# USB_Hub_PCB.net
KiCad netlist of a schematic drawn in EasyEDA Pro
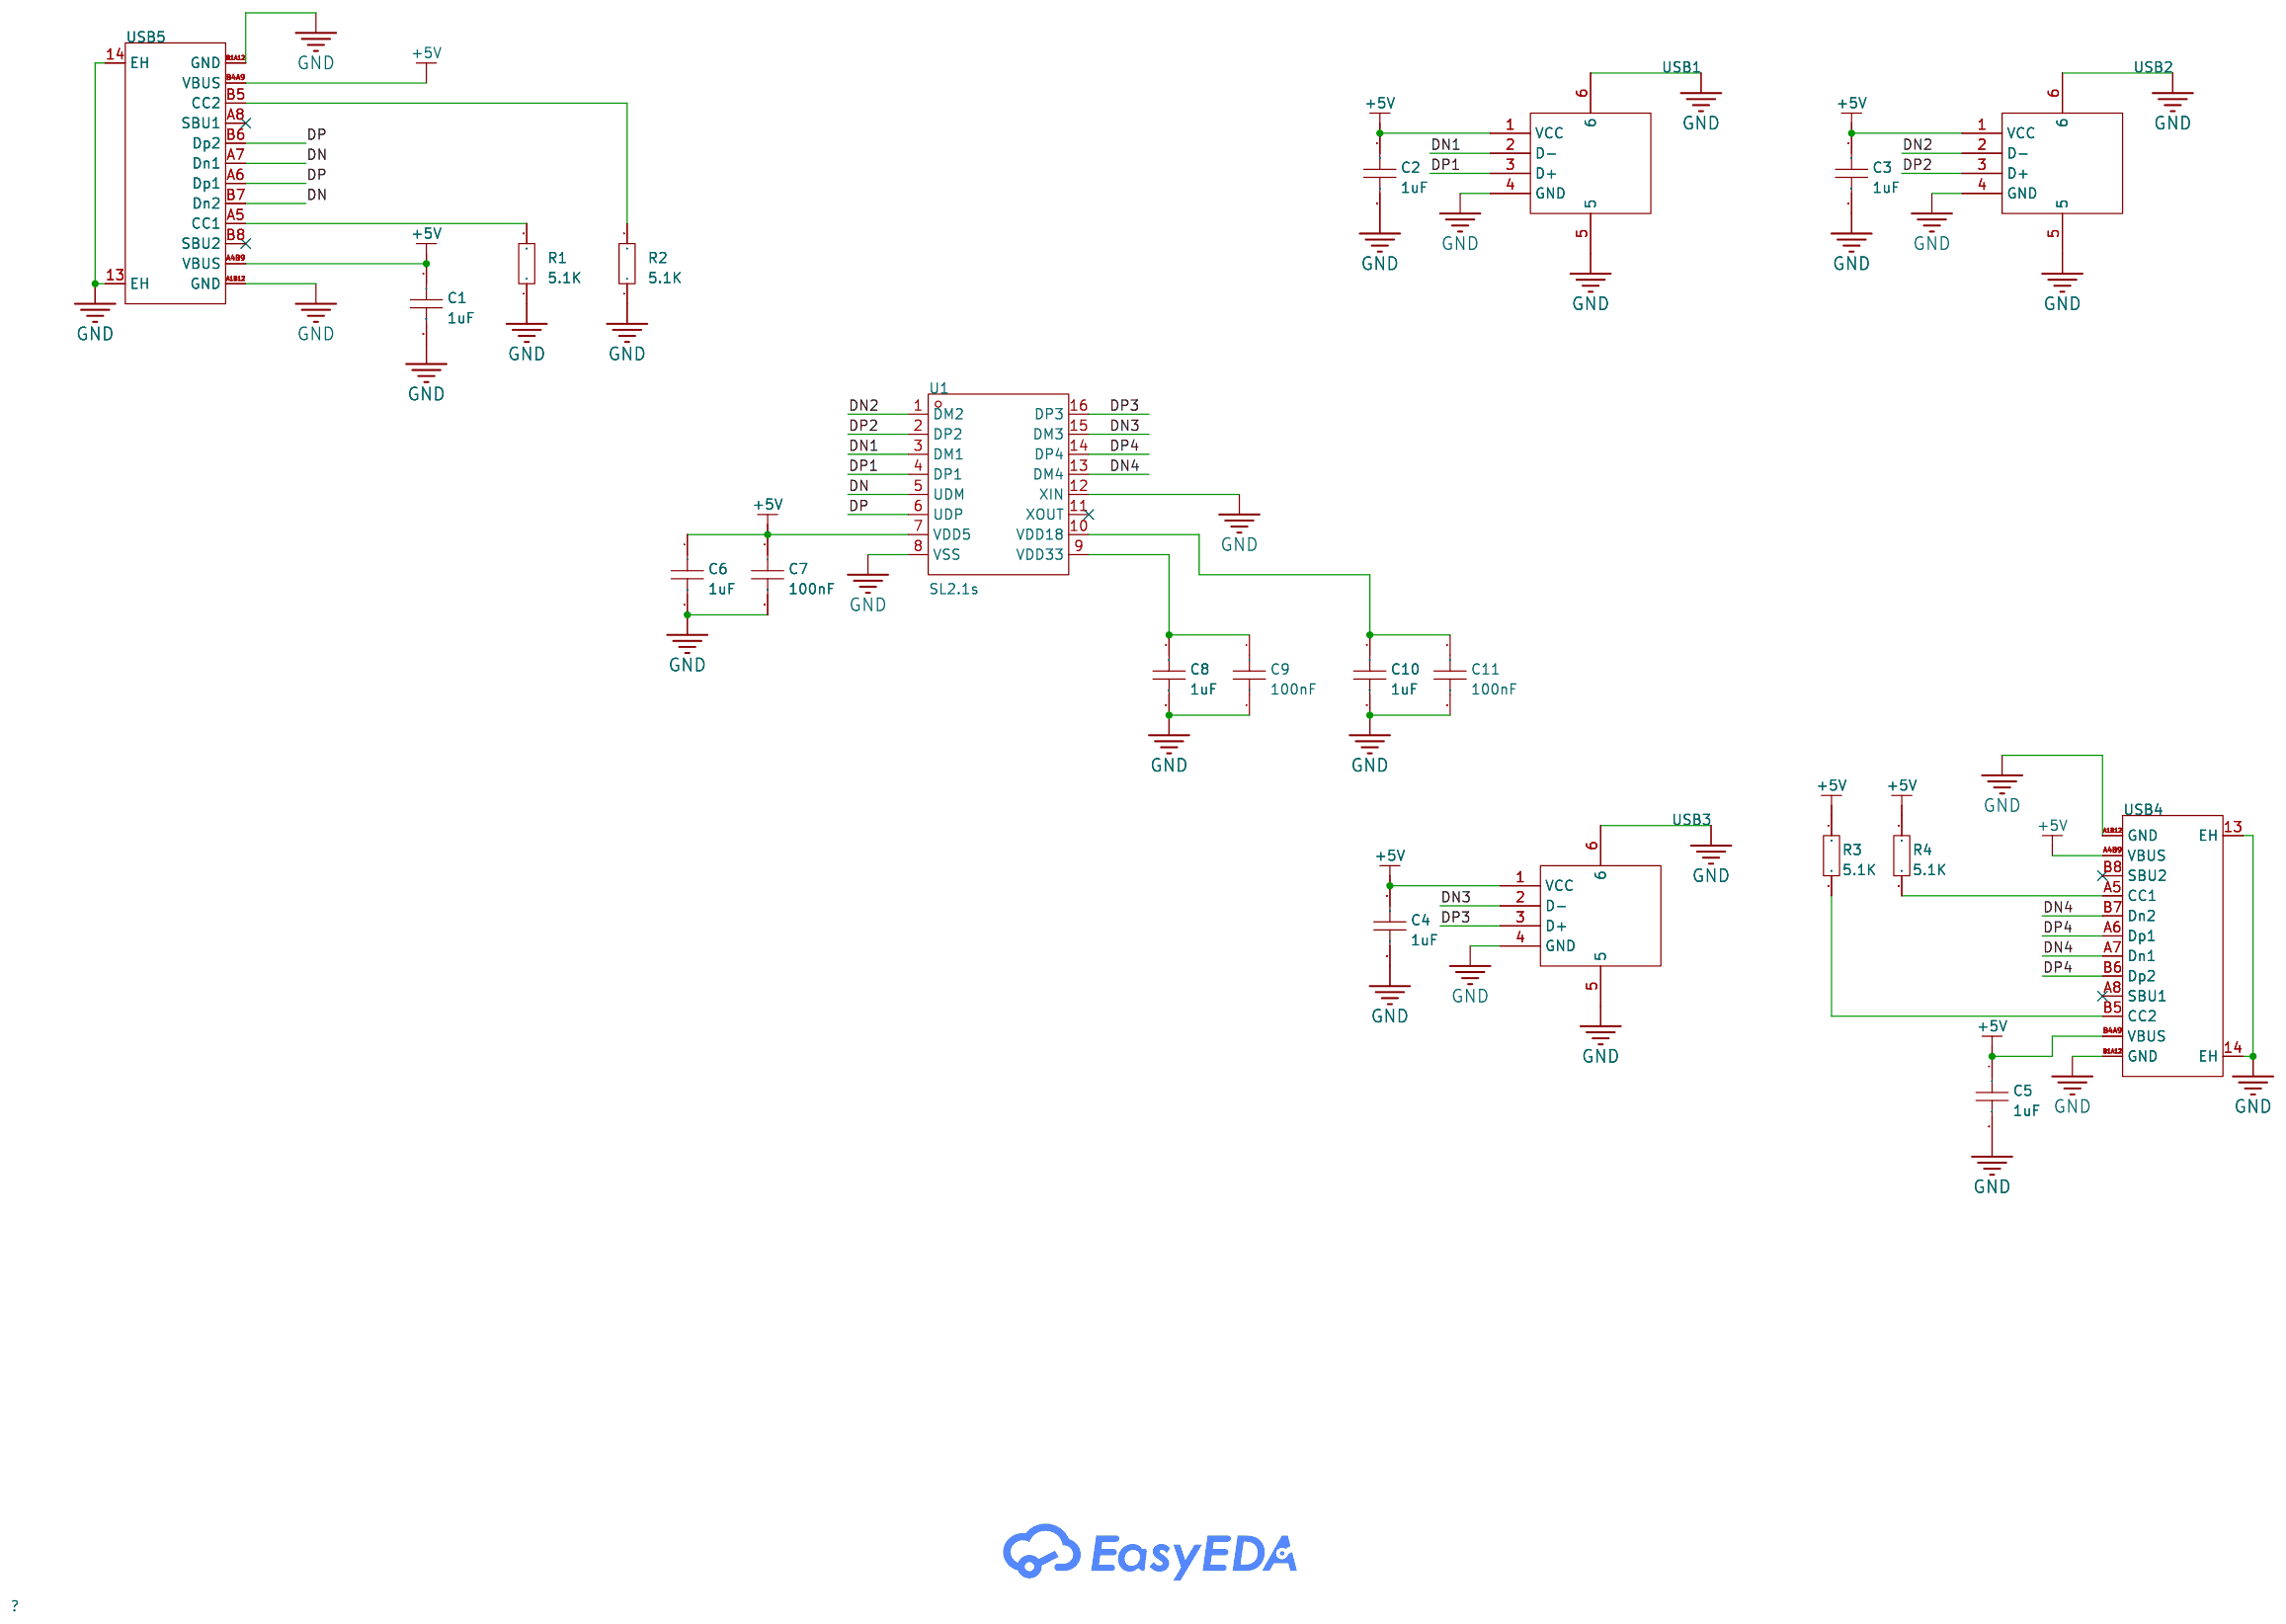
[diagram p0: schematic sheet]

(export (version "E")
  (design (tool "Eeschema 10.0.6"))
  (components
    (comp (ref "C1") (value "1uF") (footprint "easyedapro:C0603") (libsource (lib "easyedapro") (part "CAP")))
    (comp (ref "C2") (value "1uF") (footprint "easyedapro:C0603") (libsource (lib "easyedapro") (part "CAP")))
    (comp (ref "C3") (value "1uF") (footprint "easyedapro:C0603") (libsource (lib "easyedapro") (part "CAP")))
    (comp (ref "C4") (value "1uF") (footprint "easyedapro:C0603") (libsource (lib "easyedapro") (part "CAP")))
    (comp (ref "C5") (value "1uF") (footprint "easyedapro:C0603") (libsource (lib "easyedapro") (part "CAP")))
    (comp (ref "C6") (value "1uF") (footprint "easyedapro:C0603") (libsource (lib "easyedapro") (part "CAP")))
    (comp (ref "C7")
      (value "100nF")
      (footprint "easyedapro:C0603")
      (libsource (lib "easyedapro") (part "CAP"))
    )
    (comp (ref "C8") (value "1uF") (footprint "easyedapro:C0603") (libsource (lib "easyedapro") (part "CAP")))
    (comp (ref "C9")
      (value "100nF")
      (footprint "easyedapro:C0603")
      (libsource (lib "easyedapro") (part "CAP"))
    )
    (comp (ref "C10")
      (value "1uF")
      (footprint "easyedapro:C0603")
      (libsource (lib "easyedapro") (part "CAP"))
    )
    (comp (ref "C11")
      (value "100nF")
      (footprint "easyedapro:C0603")
      (libsource (lib "easyedapro") (part "CAP"))
    )
    (comp (ref "R1")
      (value "5.1K")
      (footprint "easyedapro:R0603")
      (libsource (lib "easyedapro") (part "Res"))
    )
    (comp (ref "R2")
      (value "5.1K")
      (footprint "easyedapro:R0603")
      (libsource (lib "easyedapro") (part "Res"))
    )
    (comp (ref "R3")
      (value "5.1K")
      (footprint "easyedapro:R0603")
      (libsource (lib "easyedapro") (part "Res"))
    )
    (comp (ref "R4")
      (value "5.1K")
      (footprint "easyedapro:R0603")
      (libsource (lib "easyedapro") (part "Res"))
    )
    (comp (ref "U1")
      (value "SL2.1s")
      (footprint "easyedapro:SSOP-16_L4.6-W2.6-P0.53-LS4.0-BL")
      (fields (field (name "Manufacturer") "CoreChips(和芯润德)"))
      (libsource (lib "easyedapro") (part "SL2.1S"))
    )
    (comp (ref "USB1")
      (value "10.0 QHHTZB6.3")
      (footprint "easyedapro:USB-A-TH_10.0QHHTZB6.3")
      (fields (field (name "Manufacturer") "SHOU HAN(首韩)"))
      (libsource (lib "easyedapro") (part "10.0 QHHTZB6.3"))
    )
    (comp (ref "USB2")
      (value "10.0 QHHTZB6.3")
      (footprint "easyedapro:USB-A-TH_10.0QHHTZB6.3")
      (fields (field (name "Manufacturer") "SHOU HAN(首韩)"))
      (libsource (lib "easyedapro") (part "10.0 QHHTZB6.3"))
    )
    (comp (ref "USB3")
      (value "10.0 QHHTZB6.3")
      (footprint "easyedapro:USB-A-TH_10.0QHHTZB6.3")
      (fields (field (name "Manufacturer") "SHOU HAN(首韩)"))
      (libsource (lib "easyedapro") (part "10.0 QHHTZB6.3"))
    )
    (comp (ref "USB4")
      (value "TYPE-C 16PIN 2MD(073)")
      (footprint "easyedapro:USB-C-SMD_TYPE-C-16PIN-2MD-073")
      (fields (field (name "Manufacturer") "SHOU HAN(首韩)"))
      (libsource (lib "easyedapro") (part "TYPE-C 16PIN 2MD(073)"))
    )
    (comp (ref "USB5")
      (value "TYPE-C 16PIN 2MD(073)")
      (footprint "easyedapro:USB-C-SMD_TYPE-C-16PIN-2MD-073")
      (fields (field (name "Manufacturer") "SHOU HAN(首韩)"))
      (libsource (lib "easyedapro") (part "TYPE-C 16PIN 2MD(073)"))
    )
  )
  (nets
    (net (code "1") (name "+5V") (class "Default")
      (node (ref "C1") (pin "1") (pinfunction "1_1") (pintype "input"))
      (node (ref "C2") (pin "1") (pinfunction "1_1") (pintype "input"))
      (node (ref "C3") (pin "1") (pinfunction "1_1") (pintype "input"))
      (node (ref "C4") (pin "1") (pinfunction "1_1") (pintype "input"))
      (node (ref "C5") (pin "1") (pinfunction "1_1") (pintype "input"))
      (node (ref "C6") (pin "1") (pinfunction "1_1") (pintype "input"))
      (node (ref "C7") (pin "1") (pinfunction "1_1") (pintype "input"))
      (node (ref "R3") (pin "1") (pinfunction "1_1") (pintype "input"))
      (node (ref "R4") (pin "1") (pinfunction "1_1") (pintype "input"))
      (node (ref "U1") (pin "7") (pinfunction "VDD5_7") (pintype "unspecified"))
      (node (ref "USB1") (pin "1") (pinfunction "VCC_1") (pintype "unspecified"))
      (node (ref "USB2") (pin "1") (pinfunction "VCC_1") (pintype "unspecified"))
      (node (ref "USB3") (pin "1") (pinfunction "VCC_1") (pintype "unspecified"))
      (node (ref "USB4") (pin "A4B9") (pinfunction "VBUS_A4B9") (pintype "unspecified"))
      (node (ref "USB4") (pin "B4A9") (pinfunction "VBUS_B4A9") (pintype "unspecified"))
      (node (ref "USB5") (pin "A4B9") (pinfunction "VBUS_A4B9") (pintype "unspecified"))
      (node (ref "USB5") (pin "B4A9") (pinfunction "VBUS_B4A9") (pintype "unspecified"))
    )
    (net (code "2") (name "/DN") (class "Default")
      (node (ref "U1") (pin "5") (pinfunction "UDM_5") (pintype "unspecified"))
      (node (ref "USB5") (pin "A7") (pinfunction "Dn1_A7") (pintype "unspecified"))
      (node (ref "USB5") (pin "B7") (pinfunction "Dn2_B7") (pintype "unspecified"))
    )
    (net (code "3") (name "/DN1") (class "Default")
      (node (ref "U1") (pin "3") (pinfunction "DM1_3") (pintype "unspecified"))
      (node (ref "USB1") (pin "2") (pinfunction "D-_2") (pintype "unspecified"))
    )
    (net (code "4") (name "/DN2") (class "Default")
      (node (ref "U1") (pin "1") (pinfunction "DM2_1") (pintype "unspecified"))
      (node (ref "USB2") (pin "2") (pinfunction "D-_2") (pintype "unspecified"))
    )
    (net (code "5") (name "/DN3") (class "Default")
      (node (ref "U1") (pin "15") (pinfunction "DM3_15") (pintype "unspecified"))
      (node (ref "USB3") (pin "2") (pinfunction "D-_2") (pintype "unspecified"))
    )
    (net (code "6") (name "/DN4") (class "Default")
      (node (ref "U1") (pin "13") (pinfunction "DM4_13") (pintype "unspecified"))
      (node (ref "USB4") (pin "A7") (pinfunction "Dn1_A7") (pintype "unspecified"))
      (node (ref "USB4") (pin "B7") (pinfunction "Dn2_B7") (pintype "unspecified"))
    )
    (net (code "7") (name "/DP") (class "Default")
      (node (ref "U1") (pin "6") (pinfunction "UDP_6") (pintype "unspecified"))
      (node (ref "USB5") (pin "A6") (pinfunction "Dp1_A6") (pintype "unspecified"))
      (node (ref "USB5") (pin "B6") (pinfunction "Dp2_B6") (pintype "unspecified"))
    )
    (net (code "8") (name "/DP1") (class "Default")
      (node (ref "U1") (pin "4") (pinfunction "DP1_4") (pintype "unspecified"))
      (node (ref "USB1") (pin "3") (pinfunction "D+_3") (pintype "unspecified"))
    )
    (net (code "9") (name "/DP2") (class "Default")
      (node (ref "U1") (pin "2") (pinfunction "DP2_2") (pintype "unspecified"))
      (node (ref "USB2") (pin "3") (pinfunction "D+_3") (pintype "unspecified"))
    )
    (net (code "10") (name "/DP3") (class "Default")
      (node (ref "U1") (pin "16") (pinfunction "DP3_16") (pintype "unspecified"))
      (node (ref "USB3") (pin "3") (pinfunction "D+_3") (pintype "unspecified"))
    )
    (net (code "11") (name "/DP4") (class "Default")
      (node (ref "U1") (pin "14") (pinfunction "DP4_14") (pintype "unspecified"))
      (node (ref "USB4") (pin "A6") (pinfunction "Dp1_A6") (pintype "unspecified"))
      (node (ref "USB4") (pin "B6") (pinfunction "Dp2_B6") (pintype "unspecified"))
    )
    (net (code "12") (name "GND") (class "Default")
      (node (ref "C1") (pin "2") (pinfunction "2_2") (pintype "input"))
      (node (ref "C10") (pin "2") (pinfunction "2_2") (pintype "input"))
      (node (ref "C11") (pin "2") (pinfunction "2_2") (pintype "input"))
      (node (ref "C2") (pin "2") (pinfunction "2_2") (pintype "input"))
      (node (ref "C3") (pin "2") (pinfunction "2_2") (pintype "input"))
      (node (ref "C4") (pin "2") (pinfunction "2_2") (pintype "input"))
      (node (ref "C5") (pin "2") (pinfunction "2_2") (pintype "input"))
      (node (ref "C6") (pin "2") (pinfunction "2_2") (pintype "input"))
      (node (ref "C7") (pin "2") (pinfunction "2_2") (pintype "input"))
      (node (ref "C8") (pin "2") (pinfunction "2_2") (pintype "input"))
      (node (ref "C9") (pin "2") (pinfunction "2_2") (pintype "input"))
      (node (ref "R1") (pin "1") (pinfunction "1_1") (pintype "input"))
      (node (ref "R2") (pin "1") (pinfunction "1_1") (pintype "input"))
      (node (ref "U1") (pin "12") (pinfunction "XIN_12") (pintype "unspecified"))
      (node (ref "U1") (pin "8") (pinfunction "VSS_8") (pintype "unspecified"))
      (node (ref "USB1") (pin "4") (pinfunction "GND_4") (pintype "unspecified"))
      (node (ref "USB1") (pin "5") (pinfunction "5_5") (pintype "unspecified"))
      (node (ref "USB1") (pin "6") (pinfunction "6_6") (pintype "unspecified"))
      (node (ref "USB2") (pin "4") (pinfunction "GND_4") (pintype "unspecified"))
      (node (ref "USB2") (pin "5") (pinfunction "5_5") (pintype "unspecified"))
      (node (ref "USB2") (pin "6") (pinfunction "6_6") (pintype "unspecified"))
      (node (ref "USB3") (pin "4") (pinfunction "GND_4") (pintype "unspecified"))
      (node (ref "USB3") (pin "5") (pinfunction "5_5") (pintype "unspecified"))
      (node (ref "USB3") (pin "6") (pinfunction "6_6") (pintype "unspecified"))
      (node (ref "USB4") (pin "13") (pinfunction "EH_13") (pintype "unspecified"))
      (node (ref "USB4") (pin "14") (pinfunction "EH_14") (pintype "unspecified"))
      (node (ref "USB4") (pin "A1B12") (pinfunction "GND_A1B12") (pintype "unspecified"))
      (node (ref "USB4") (pin "B1A12") (pinfunction "GND_B1A12") (pintype "unspecified"))
      (node (ref "USB5") (pin "13") (pinfunction "EH_13") (pintype "unspecified"))
      (node (ref "USB5") (pin "14") (pinfunction "EH_14") (pintype "unspecified"))
      (node (ref "USB5") (pin "A1B12") (pinfunction "GND_A1B12") (pintype "unspecified"))
      (node (ref "USB5") (pin "B1A12") (pinfunction "GND_B1A12") (pintype "unspecified"))
    )
    (net (code "13") (name "Net-(U1-VDD18)") (class "Default")
      (node (ref "C10") (pin "1") (pinfunction "1_1") (pintype "input"))
      (node (ref "C11") (pin "1") (pinfunction "1_1") (pintype "input"))
      (node (ref "U1") (pin "10") (pinfunction "VDD18_10") (pintype "unspecified"))
    )
    (net (code "14") (name "Net-(U1-VDD33)") (class "Default")
      (node (ref "C8") (pin "1") (pinfunction "1_1") (pintype "input"))
      (node (ref "C9") (pin "1") (pinfunction "1_1") (pintype "input"))
      (node (ref "U1") (pin "9") (pinfunction "VDD33_9") (pintype "unspecified"))
    )
    (net (code "15") (name "Net-(USB4-CC1)") (class "Default")
      (node (ref "R4") (pin "2") (pinfunction "2_2") (pintype "input"))
      (node (ref "USB4") (pin "A5") (pinfunction "CC1_A5") (pintype "unspecified"))
    )
    (net (code "16") (name "Net-(USB4-CC2)") (class "Default")
      (node (ref "R3") (pin "2") (pinfunction "2_2") (pintype "input"))
      (node (ref "USB4") (pin "B5") (pinfunction "CC2_B5") (pintype "unspecified"))
    )
    (net (code "17") (name "Net-(USB5-CC1)") (class "Default")
      (node (ref "R1") (pin "2") (pinfunction "2_2") (pintype "input"))
      (node (ref "USB5") (pin "A5") (pinfunction "CC1_A5") (pintype "unspecified"))
    )
    (net (code "18") (name "Net-(USB5-CC2)") (class "Default")
      (node (ref "R2") (pin "2") (pinfunction "2_2") (pintype "input"))
      (node (ref "USB5") (pin "B5") (pinfunction "CC2_B5") (pintype "unspecified"))
    )
    (net (code "19") (name "unconnected-(U1-XOUT-Pad11)") (class "Default")
      (node (ref "U1") (pin "11") (pinfunction "XOUT_11") (pintype "unspecified+no_connect"))
    )
    (net (code "20") (name "unconnected-(USB4-SBU1-PadA8)") (class "Default")
      (node (ref "USB4") (pin "A8") (pinfunction "SBU1_A8") (pintype "unspecified+no_connect"))
    )
    (net (code "21") (name "unconnected-(USB4-SBU2-PadB8)") (class "Default")
      (node (ref "USB4") (pin "B8") (pinfunction "SBU2_B8") (pintype "unspecified+no_connect"))
    )
    (net (code "22") (name "unconnected-(USB5-SBU1-PadA8)") (class "Default")
      (node (ref "USB5") (pin "A8") (pinfunction "SBU1_A8") (pintype "unspecified+no_connect"))
    )
    (net (code "23") (name "unconnected-(USB5-SBU2-PadB8)") (class "Default")
      (node (ref "USB5") (pin "B8") (pinfunction "SBU2_B8") (pintype "unspecified+no_connect"))
    )
  )
)
